# Sheet1.net
KiCad netlist of a schematic drawn in Altium Designer
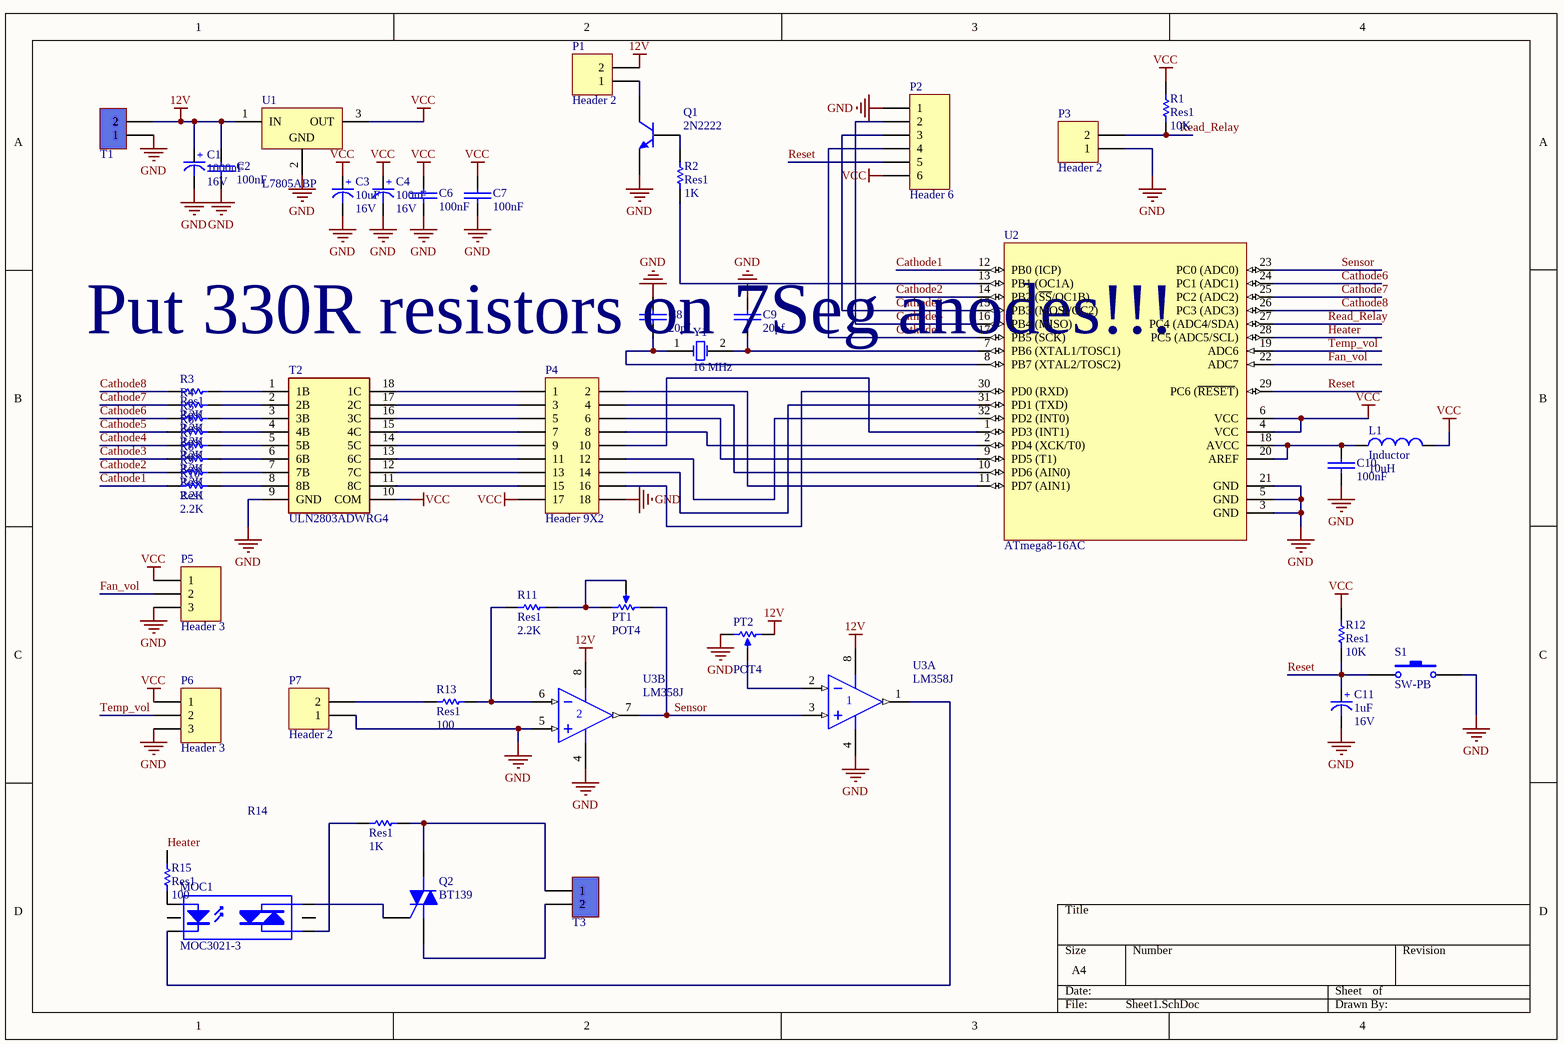
[diagram p0: Sheet1.SchDoc]

(export (version "E")
  (design (tool "Eeschema 10.0.6"))
  (components
    (comp (ref "C1")
      (value "1000uF")
      (footprint "cap 04")
      (description "Polar Capacitor")
      (fields (field (name "VOLTAGE") "16V") (field (name "DESIGNER") "Saeid Jorablo"))
      (libsource (lib "My_Library") (part "Cap-Polar"))
    )
    (comp (ref "C2")
      (value "100nF")
      (footprint "Cap - 100nF")
      (description "Bipolar Capacitor")
      (fields (field (name "VOLTAGE") "100V") (field (name "DESIGNER") "Saeid Jorablo"))
      (libsource (lib "My_Library") (part "Cap-Bipolar"))
    )
    (comp (ref "C3")
      (value "10uF")
      (footprint "cap 02")
      (description "Polar Capacitor")
      (fields (field (name "VOLTAGE") "16V") (field (name "DESIGNER") "Saeid Jorablo"))
      (libsource (lib "My_Library") (part "Cap-Polar"))
    )
    (comp (ref "C4")
      (value "100uF")
      (footprint "cap 03")
      (description "Polar Capacitor")
      (fields (field (name "VOLTAGE") "16V") (field (name "DESIGNER") "Saeid Jorablo"))
      (libsource (lib "My_Library") (part "Cap-Polar"))
    )
    (comp (ref "C6")
      (value "100nF")
      (footprint "CAP 1206 (3216X15L)")
      (description "Bipolar Capacitor")
      (fields (field (name "VOLTAGE") "100V") (field (name "DESIGNER") "Saeid Jorablo"))
      (libsource (lib "My_Library") (part "Cap-Bipolar"))
    )
    (comp (ref "C7")
      (value "100nF")
      (footprint "CAP 1206 (3216X15L)")
      (description "Bipolar Capacitor")
      (fields (field (name "VOLTAGE") "100V") (field (name "DESIGNER") "Saeid Jorablo"))
      (libsource (lib "My_Library") (part "Cap-Bipolar"))
    )
    (comp (ref "C8")
      (value "20pf")
      (footprint "CAP 1206 (3216X15L)")
      (description "Bipolar Capacitor")
      (fields (field (name "VOLTAGE") "100V") (field (name "DESIGNER") "Saeid Jorablo"))
      (libsource (lib "My_Library") (part "Cap-Bipolar"))
    )
    (comp (ref "C9")
      (value "20pf")
      (footprint "CAP 1206 (3216X15L)")
      (description "Bipolar Capacitor")
      (fields (field (name "VOLTAGE") "100V") (field (name "DESIGNER") "Saeid Jorablo"))
      (libsource (lib "My_Library") (part "Cap-Bipolar"))
    )
    (comp (ref "C10")
      (value "100nF")
      (footprint "CAP 1206 (3216X15L)")
      (description "Bipolar Capacitor")
      (fields (field (name "VOLTAGE") "100V") (field (name "DESIGNER") "Saeid Jorablo"))
      (libsource (lib "My_Library") (part "Cap-Bipolar"))
    )
    (comp (ref "C11")
      (value "1uF")
      (footprint "cap 00")
      (description "Polar Capacitor")
      (fields (field (name "VOLTAGE") "16V") (field (name "DESIGNER") "Saeid Jorablo"))
      (libsource (lib "My_Library") (part "Cap-Polar"))
    )
    (comp (ref "L1")
      (value "Inductor")
      (footprint "AXIAL-0.4")
      (fields (field (name "ALTIUM_VALUE") "10uH") (field (name "PUBLISHER") "Altium Limited"))
      (libsource (lib "Miscellaneous Devices") (part "Inductor"))
    )
    (comp (ref "MOC1")
      (value "MOC3021-3")
      (footprint "DIP-6")
      (description "Opto-Triac")
      (fields
        (field (name "PUBLISHER") "www.picpars.com")
        (field (name "DESIGNER") "Seyed Mohsen Ghasemian")
        (field (name "E-MAIL") "picpars@gmail.com")
      )
      (libsource (lib "usefully_Library") (part "MOC3021-3"))
    )
    (comp (ref "P1")
      (value "Header 2")
      (footprint "HDR1X2")
      (description "Header, 2-Pin")
      (fields (field (name "PUBLISHER") "Altium Limited"))
      (libsource (lib "Miscellaneous Connectors") (part "Header 2"))
    )
    (comp (ref "P2")
      (value "Header 6")
      (footprint "HDR1X6")
      (description "Header, 6-Pin")
      (fields (field (name "PUBLISHER") "Altium Limited"))
      (libsource (lib "Miscellaneous Connectors") (part "Header 6"))
    )
    (comp (ref "P3")
      (value "Header 2")
      (footprint "HDR1X2")
      (description "Header, 2-Pin")
      (fields (field (name "PUBLISHER") "Altium Limited"))
      (libsource (lib "Miscellaneous Connectors") (part "Header 2"))
    )
    (comp (ref "P4")
      (value "Header 9X2")
      (footprint "HDR2X9")
      (description "Header, 9-Pin, Dual row")
      (fields (field (name "PUBLISHER") "Altium Limited"))
      (libsource (lib "Miscellaneous Connectors") (part "Header 9X2"))
    )
    (comp (ref "P5")
      (value "Header 3")
      (footprint "HDR1X3")
      (description "Header, 3-Pin")
      (fields (field (name "PUBLISHER") "Altium Limited"))
      (libsource (lib "Miscellaneous Connectors") (part "Header 3"))
    )
    (comp (ref "P6")
      (value "Header 3")
      (footprint "HDR1X3")
      (description "Header, 3-Pin")
      (fields (field (name "PUBLISHER") "Altium Limited"))
      (libsource (lib "Miscellaneous Connectors") (part "Header 3"))
    )
    (comp (ref "P7")
      (value "Header 2")
      (footprint "HDR1X2")
      (description "Header, 2-Pin")
      (fields (field (name "PUBLISHER") "Altium Limited"))
      (libsource (lib "Miscellaneous Connectors") (part "Header 2"))
    )
    (comp (ref "PT1")
      (value "POT4")
      (footprint "POT4")
      (description "Variable Potentiometer top adjust")
      (fields (field (name "DESIGNER") "Seyed Mohsen Ghasemian"))
      (libsource (lib "usefully_Library") (part "POT4"))
    )
    (comp (ref "PT2")
      (value "POT4")
      (footprint "POT4")
      (description "Variable Potentiometer top adjust")
      (fields (field (name "DESIGNER") "Seyed Mohsen Ghasemian"))
      (libsource (lib "usefully_Library") (part "POT4"))
    )
    (comp (ref "Q1")
      (value "2N2222")
      (footprint "T4-TO92")
      (description "NPN")
      (fields (field (name "E-MAIL") "picpars@gmail.com"))
      (libsource (lib "usefully_Library") (part "2N2222"))
    )
    (comp (ref "Q2")
      (value "BT139")
      (footprint "TO-220-AB")
      (description "Silicon Bidirectional Triode Thyristor")
      (fields (field (name "PUBLISHER") "Altium Limited"))
      (libsource (lib "Motorola Discrete TRIAC") (part "MAC15A6"))
    )
    (comp (ref "R1")
      (value "Res1")
      (footprint "AXIAL-0.3")
      (description "Resistor")
      (fields (field (name "ALTIUM_VALUE") "10K") (field (name "PUBLISHER") "Altium Limited"))
      (libsource (lib "Miscellaneous Devices") (part "Res1"))
    )
    (comp (ref "R2")
      (value "Res1")
      (footprint "AXIAL-0.3")
      (description "Resistor")
      (fields (field (name "ALTIUM_VALUE") "1K") (field (name "PUBLISHER") "Altium Limited"))
      (libsource (lib "Miscellaneous Devices") (part "Res1"))
    )
    (comp (ref "R3")
      (value "Res1")
      (footprint "AXIAL-0.3")
      (description "Resistor")
      (fields (field (name "ALTIUM_VALUE") "2.2K") (field (name "PUBLISHER") "Altium Limited"))
      (libsource (lib "Miscellaneous Devices") (part "Res1"))
    )
    (comp (ref "R4")
      (value "Res1")
      (footprint "AXIAL-0.3")
      (description "Resistor")
      (fields (field (name "ALTIUM_VALUE") "2.2K") (field (name "PUBLISHER") "Altium Limited"))
      (libsource (lib "Miscellaneous Devices") (part "Res1"))
    )
    (comp (ref "R5")
      (value "Res1")
      (footprint "AXIAL-0.3")
      (description "Resistor")
      (fields (field (name "ALTIUM_VALUE") "2.2K") (field (name "PUBLISHER") "Altium Limited"))
      (libsource (lib "Miscellaneous Devices") (part "Res1"))
    )
    (comp (ref "R6")
      (value "Res1")
      (footprint "AXIAL-0.3")
      (description "Resistor")
      (fields (field (name "ALTIUM_VALUE") "2.2K") (field (name "PUBLISHER") "Altium Limited"))
      (libsource (lib "Miscellaneous Devices") (part "Res1"))
    )
    (comp (ref "R7")
      (value "Res1")
      (footprint "AXIAL-0.3")
      (description "Resistor")
      (fields (field (name "ALTIUM_VALUE") "2.2K") (field (name "PUBLISHER") "Altium Limited"))
      (libsource (lib "Miscellaneous Devices") (part "Res1"))
    )
    (comp (ref "R8")
      (value "Res1")
      (footprint "AXIAL-0.3")
      (description "Resistor")
      (fields (field (name "ALTIUM_VALUE") "2.2K") (field (name "PUBLISHER") "Altium Limited"))
      (libsource (lib "Miscellaneous Devices") (part "Res1"))
    )
    (comp (ref "R9")
      (value "Res1")
      (footprint "AXIAL-0.3")
      (description "Resistor")
      (fields (field (name "ALTIUM_VALUE") "2.2K") (field (name "PUBLISHER") "Altium Limited"))
      (libsource (lib "Miscellaneous Devices") (part "Res1"))
    )
    (comp (ref "R10")
      (value "Res1")
      (footprint "AXIAL-0.3")
      (description "Resistor")
      (fields (field (name "ALTIUM_VALUE") "2.2K") (field (name "PUBLISHER") "Altium Limited"))
      (libsource (lib "Miscellaneous Devices") (part "Res1"))
    )
    (comp (ref "R11")
      (value "Res1")
      (footprint "AXIAL-0.3")
      (description "Resistor")
      (fields (field (name "ALTIUM_VALUE") "2.2K") (field (name "PUBLISHER") "Altium Limited"))
      (libsource (lib "Miscellaneous Devices") (part "Res1"))
    )
    (comp (ref "R12")
      (value "Res1")
      (footprint "AXIAL-0.3")
      (description "Resistor")
      (fields (field (name "ALTIUM_VALUE") "10K") (field (name "PUBLISHER") "Altium Limited"))
      (libsource (lib "Miscellaneous Devices") (part "Res1"))
    )
    (comp (ref "R13")
      (value "Res1")
      (footprint "AXIAL-0.3")
      (description "Resistor")
      (fields (field (name "ALTIUM_VALUE") "100") (field (name "PUBLISHER") "Altium Limited"))
      (libsource (lib "Miscellaneous Devices") (part "Res1"))
    )
    (comp (ref "R14")
      (value "Res1")
      (footprint "AXIAL-0.3")
      (description "Resistor")
      (fields (field (name "ALTIUM_VALUE") "1K") (field (name "PUBLISHER") "Altium Limited"))
      (libsource (lib "Miscellaneous Devices") (part "Res1"))
    )
    (comp (ref "R15")
      (value "Res1")
      (footprint "AXIAL-0.3")
      (description "Resistor")
      (fields (field (name "ALTIUM_VALUE") "100") (field (name "PUBLISHER") "Altium Limited"))
      (libsource (lib "Miscellaneous Devices") (part "Res1"))
    )
    (comp (ref "S1")
      (value "SW-PB")
      (footprint "SPST-2")
      (description "Switch")
      (fields (field (name "PUBLISHER") "Altium Limited"))
      (libsource (lib "Miscellaneous Devices") (part "SW-PB"))
    )
    (comp (ref "T1")
      (value "Terminal")
      (footprint "Terminal 1*2")
      (description "Terminal 2 Pin 250VAC 16A")
      (fields (field (name "DESIGNER") "Seyed Mohsen Ghasemain") (field (name "E-MAIL") "picpars@gmail.com"))
      (libsource (lib "usefully_Library") (part "Terminal 1*2"))
    )
    (comp (ref "T2")
      (value "ULN2803ADWRG4")
      (footprint "SamacSys:SOIC127P1030X265-18N")
      (description "Transformer")
      (fields (field (name "MOUSER PART NUMBER") "595-ULN2803ADWRG4"))
      (libsource (lib "*") (part "ULN2803ADWRG4"))
    )
    (comp (ref "T3")
      (value "Terminal")
      (footprint "Terminal 1*2")
      (description "Terminal 2 Pin 250VAC 16A")
      (fields (field (name "DESIGNER") "Seyed Mohsen Ghasemain") (field (name "E-MAIL") "picpars@gmail.com"))
      (libsource (lib "PicPars.com_usefully_Library") (part "Terminal 1*2"))
    )
    (comp (ref "U1")
      (value "L7805ABP")
      (footprint "TO220FP")
      (description "Positive Voltage Regulator, 5V, 3-Pin TO-220FP")
      (libsource (lib "STMicroelectronics Power Management Linear Regulator") (part "L7805ABP"))
    )
    (comp (ref "U2")
      (value "ATmega8-16AC")
      (footprint "32A_M")
      (description "8-Bit AVR Microcontroller with 8K Bytes of In-System Programmable Flash Memory")
      (fields (field (name "PUBLISHER") "Altium Limited"))
      (libsource (lib "Atmel Microcontroller 8-Bit AVR") (part "ATmega8-16AC"))
    )
    (comp (ref "U3")
      (value "LM358J")
      (footprint "693-02")
      (description "Dual Low-Power Operational Amplifier")
      (fields (field (name "PUBLISHER") "Altium Limited"))
      (libsource (lib "Motorola Amplifier Operational Amplifier") (part "LM358J"))
    )
    (comp (ref "Y1")
      (value "16 MHz")
      (footprint "XTAL")
      (description "XTAL Crystal")
      (libsource (lib "My_Library") (part "XTAL"))
    )
  )
  (nets
    (net (code "1") (name "/Cathode1") (class "Default")
      (node (ref "R10") (pin "1") (pinfunction "1_1") (pintype "passive"))
      (node (ref "U2") (pin "12") (pinfunction "PB0_(ICP)_12") (pintype "bidirectional"))
    )
    (net (code "2") (name "/Cathode2") (class "Default")
      (node (ref "R9") (pin "1") (pinfunction "1_1") (pintype "passive"))
      (node (ref "U2") (pin "14") (pinfunction "PB2_(~{SS}/OC1B)_14") (pintype "bidirectional"))
    )
    (net (code "3") (name "/Cathode3") (class "Default")
      (node (ref "P2") (pin "3") (pinfunction "3_3") (pintype "passive"))
      (node (ref "R8") (pin "1") (pinfunction "1_1") (pintype "passive"))
      (node (ref "U2") (pin "15") (pinfunction "PB3_(MOSI/OC2)_15") (pintype "bidirectional"))
    )
    (net (code "4") (name "/Cathode4") (class "Default")
      (node (ref "P2") (pin "2") (pinfunction "2_2") (pintype "passive"))
      (node (ref "R7") (pin "1") (pinfunction "1_1") (pintype "passive"))
      (node (ref "U2") (pin "16") (pinfunction "PB4_(MISO)_16") (pintype "bidirectional"))
    )
    (net (code "5") (name "/Cathode5") (class "Default")
      (node (ref "P2") (pin "4") (pinfunction "4_4") (pintype "passive"))
      (node (ref "R6") (pin "1") (pinfunction "1_1") (pintype "passive"))
      (node (ref "U2") (pin "17") (pinfunction "PB5_(SCK)_17") (pintype "bidirectional"))
    )
    (net (code "6") (name "/Cathode6") (class "Default")
      (node (ref "R5") (pin "1") (pinfunction "1_1") (pintype "passive"))
      (node (ref "U2") (pin "24") (pinfunction "PC1_(ADC1)_24") (pintype "bidirectional"))
    )
    (net (code "7") (name "/Cathode7") (class "Default")
      (node (ref "R4") (pin "1") (pinfunction "1_1") (pintype "passive"))
      (node (ref "U2") (pin "25") (pinfunction "PC2_(ADC2)_25") (pintype "bidirectional"))
    )
    (net (code "8") (name "/Cathode8") (class "Default")
      (node (ref "R3") (pin "1") (pinfunction "1_1") (pintype "passive"))
      (node (ref "U2") (pin "26") (pinfunction "PC3_(ADC3)_26") (pintype "bidirectional"))
    )
    (net (code "9") (name "/Fan_vol") (class "Default")
      (node (ref "P5") (pin "2") (pinfunction "2_2") (pintype "passive"))
      (node (ref "U2") (pin "22") (pinfunction "ADC7_22") (pintype "input"))
    )
    (net (code "10") (name "/Heater") (class "Default")
      (node (ref "R15") (pin "1") (pinfunction "1_1") (pintype "passive"))
      (node (ref "U2") (pin "28") (pinfunction "PC5_(ADC5/SCL)_28") (pintype "bidirectional"))
    )
    (net (code "11") (name "/Read_Relay") (class "Default")
      (node (ref "P3") (pin "2") (pinfunction "2_2") (pintype "passive"))
      (node (ref "R1") (pin "2") (pinfunction "2_2") (pintype "passive"))
      (node (ref "U2") (pin "27") (pinfunction "PC4_(ADC4/SDA)_27") (pintype "bidirectional"))
    )
    (net (code "12") (name "/Reset") (class "Default")
      (node (ref "C11") (pin "1") (pinfunction "+_1") (pintype "passive"))
      (node (ref "P2") (pin "5") (pinfunction "5_5") (pintype "passive"))
      (node (ref "R12") (pin "2") (pinfunction "2_2") (pintype "passive"))
      (node (ref "S1") (pin "1") (pinfunction "1_1") (pintype "passive"))
      (node (ref "U2") (pin "29") (pinfunction "PC6_(~{RESET})_29") (pintype "bidirectional"))
    )
    (net (code "13") (name "/Sensor") (class "Default")
      (node (ref "PT1") (pin "1") (pinfunction "TOP_1") (pintype "passive"))
      (node (ref "U2") (pin "23") (pinfunction "PC0_(ADC0)_23") (pintype "bidirectional"))
      (node (ref "U3") (pin "3") (pinfunction "IN+_3") (pintype "input"))
      (node (ref "U3") (pin "7") (pinfunction "OUT_7") (pintype "output"))
    )
    (net (code "14") (name "/Temp_vol") (class "Default")
      (node (ref "P6") (pin "2") (pinfunction "2_2") (pintype "passive"))
      (node (ref "U2") (pin "19") (pinfunction "ADC6_19") (pintype "input"))
    )
    (net (code "15") (name "12V") (class "Default")
      (node (ref "C1") (pin "1") (pinfunction "+_1") (pintype "passive"))
      (node (ref "C2") (pin "1") (pinfunction "+_1") (pintype "passive"))
      (node (ref "P1") (pin "2") (pinfunction "2_2") (pintype "passive"))
      (node (ref "PT2") (pin "2") (pinfunction "BOT_2") (pintype "passive"))
      (node (ref "T1") (pin "2") (pinfunction "2_2") (pintype "passive"))
      (node (ref "U1") (pin "1") (pinfunction "IN_1") (pintype "power_in"))
      (node (ref "U3") (pin "8") (pinfunction "V+_8") (pintype "power_in"))
    )
    (net (code "16") (name "GND") (class "Default")
      (node (ref "C1") (pin "2") (pinfunction "-_2") (pintype "passive"))
      (node (ref "C10") (pin "2") (pinfunction "-_2") (pintype "passive"))
      (node (ref "C11") (pin "2") (pinfunction "-_2") (pintype "passive"))
      (node (ref "C2") (pin "2") (pinfunction "-_2") (pintype "passive"))
      (node (ref "C3") (pin "2") (pinfunction "-_2") (pintype "passive"))
      (node (ref "C4") (pin "2") (pinfunction "-_2") (pintype "passive"))
      (node (ref "C6") (pin "2") (pinfunction "-_2") (pintype "passive"))
      (node (ref "C7") (pin "2") (pinfunction "-_2") (pintype "passive"))
      (node (ref "C8") (pin "2") (pinfunction "-_2") (pintype "passive"))
      (node (ref "C9") (pin "1") (pinfunction "+_1") (pintype "passive"))
      (node (ref "P2") (pin "1") (pinfunction "1_1") (pintype "passive"))
      (node (ref "P3") (pin "1") (pinfunction "1_1") (pintype "passive"))
      (node (ref "P4") (pin "18") (pinfunction "18_18") (pintype "passive"))
      (node (ref "P5") (pin "3") (pinfunction "3_3") (pintype "passive"))
      (node (ref "P6") (pin "3") (pinfunction "3_3") (pintype "passive"))
      (node (ref "P7") (pin "1") (pinfunction "1_1") (pintype "passive"))
      (node (ref "PT2") (pin "1") (pinfunction "TOP_1") (pintype "passive"))
      (node (ref "Q1") (pin "E") (pinfunction "E_E") (pintype "passive"))
      (node (ref "S1") (pin "2") (pinfunction "2_2") (pintype "passive"))
      (node (ref "T1") (pin "1") (pinfunction "1_1") (pintype "passive"))
      (node (ref "T2") (pin "9") (pinfunction "GND_9") (pintype "passive"))
      (node (ref "U1") (pin "2") (pinfunction "GND_2") (pintype "power_in"))
      (node (ref "U2") (pin "21") (pinfunction "GND_21") (pintype "power_in"))
      (node (ref "U2") (pin "3") (pinfunction "GND_3") (pintype "power_in"))
      (node (ref "U2") (pin "5") (pinfunction "GND_5") (pintype "power_in"))
      (node (ref "U3") (pin "4") (pinfunction "V-_4") (pintype "power_in"))
      (node (ref "U3") (pin "5") (pinfunction "IN+_5") (pintype "input"))
    )
    (net (code "17") (name "Net-(C8-+)") (class "Default")
      (node (ref "C8") (pin "1") (pinfunction "+_1") (pintype "passive"))
      (node (ref "U2") (pin "8") (pinfunction "PB7_(XTAL2/TOSC2)_8") (pintype "bidirectional"))
      (node (ref "Y1") (pin "1") (pinfunction "OSC1_1") (pintype "passive"))
    )
    (net (code "18") (name "Net-(C9--)") (class "Default")
      (node (ref "C9") (pin "2") (pinfunction "-_2") (pintype "passive"))
      (node (ref "U2") (pin "7") (pinfunction "PB6_(XTAL1/TOSC1)_7") (pintype "bidirectional"))
      (node (ref "Y1") (pin "2") (pinfunction "OSC2_2") (pintype "passive"))
    )
    (net (code "19") (name "Net-(C10-+)") (class "Default")
      (node (ref "C10") (pin "1") (pinfunction "+_1") (pintype "passive"))
      (node (ref "L1") (pin "1") (pinfunction "1_1") (pintype "passive"))
      (node (ref "U2") (pin "18") (pinfunction "AVCC_18") (pintype "power_in"))
      (node (ref "U2") (pin "20") (pinfunction "AREF_20") (pintype "passive"))
    )
    (net (code "20") (name "Net-(MOC1-A)") (class "Default")
      (node (ref "MOC1") (pin "1") (pinfunction "A_1") (pintype "passive"))
      (node (ref "R15") (pin "2") (pinfunction "2_2") (pintype "passive"))
    )
    (net (code "21") (name "Net-(MOC1-A{slash}K-Pad6)") (class "Default")
      (node (ref "MOC1") (pin "6") (pinfunction "A/K_6") (pintype "passive"))
      (node (ref "R14") (pin "1") (pinfunction "1_1") (pintype "passive"))
    )
    (net (code "22") (name "Net-(MOC1-K)") (class "Default")
      (node (ref "MOC1") (pin "2") (pinfunction "K_2") (pintype "passive"))
      (node (ref "U3") (pin "1") (pinfunction "OUT_1") (pintype "output"))
    )
    (net (code "23") (name "Net-(P1-Pad1)") (class "Default")
      (node (ref "P1") (pin "1") (pinfunction "1_1") (pintype "passive"))
      (node (ref "Q1") (pin "C") (pinfunction "C_C") (pintype "passive"))
    )
    (net (code "24") (name "Net-(P7-Pad2)") (class "Default")
      (node (ref "P7") (pin "2") (pinfunction "2_2") (pintype "passive"))
      (node (ref "R13") (pin "1") (pinfunction "1_1") (pintype "passive"))
    )
    (net (code "25") (name "Net-(PT1-BOT)") (class "Default")
      (node (ref "PT1") (pin "2") (pinfunction "BOT_2") (pintype "passive"))
      (node (ref "PT1") (pin "3") (pinfunction "TAP_3") (pintype "passive"))
      (node (ref "R11") (pin "2") (pinfunction "2_2") (pintype "passive"))
    )
    (net (code "26") (name "Net-(PT2-TAP)") (class "Default")
      (node (ref "PT2") (pin "3") (pinfunction "TAP_3") (pintype "passive"))
      (node (ref "U3") (pin "2") (pinfunction "IN-_2") (pintype "input"))
    )
    (net (code "27") (name "Net-(Q1-PadB)") (class "Default")
      (node (ref "Q1") (pin "B") (pinfunction "B_B") (pintype "passive"))
      (node (ref "R2") (pin "1") (pinfunction "1_1") (pintype "passive"))
    )
    (net (code "28") (name "Net-(Q2-G)") (class "Default")
      (node (ref "MOC1") (pin "4") (pinfunction "A/K_4") (pintype "passive"))
      (node (ref "Q2") (pin "3") (pinfunction "G_3") (pintype "passive"))
    )
    (net (code "29") (name "Net-(Q2-M1)") (class "Default")
      (node (ref "Q2") (pin "1") (pinfunction "M1_1") (pintype "passive"))
      (node (ref "T3") (pin "2") (pinfunction "2_2") (pintype "passive"))
    )
    (net (code "30") (name "Net-(Q2-M2)") (class "Default")
      (node (ref "Q2") (pin "2") (pinfunction "M2_2") (pintype "passive"))
      (node (ref "R14") (pin "2") (pinfunction "2_2") (pintype "passive"))
      (node (ref "T3") (pin "1") (pinfunction "1_1") (pintype "passive"))
    )
    (net (code "31") (name "Net-(T2-1B)") (class "Default")
      (node (ref "R3") (pin "2") (pinfunction "2_2") (pintype "passive"))
      (node (ref "T2") (pin "1") (pinfunction "1B_1") (pintype "passive"))
    )
    (net (code "32") (name "Net-(T2-1C)") (class "Default")
      (node (ref "P4") (pin "1") (pinfunction "1_1") (pintype "passive"))
      (node (ref "T2") (pin "18") (pinfunction "1C_18") (pintype "passive"))
    )
    (net (code "33") (name "Net-(T2-2B)") (class "Default")
      (node (ref "R4") (pin "2") (pinfunction "2_2") (pintype "passive"))
      (node (ref "T2") (pin "2") (pinfunction "2B_2") (pintype "passive"))
    )
    (net (code "34") (name "Net-(T2-2C)") (class "Default")
      (node (ref "P4") (pin "3") (pinfunction "3_3") (pintype "passive"))
      (node (ref "T2") (pin "17") (pinfunction "2C_17") (pintype "passive"))
    )
    (net (code "35") (name "Net-(T2-3B)") (class "Default")
      (node (ref "R5") (pin "2") (pinfunction "2_2") (pintype "passive"))
      (node (ref "T2") (pin "3") (pinfunction "3B_3") (pintype "passive"))
    )
    (net (code "36") (name "Net-(T2-3C)") (class "Default")
      (node (ref "P4") (pin "5") (pinfunction "5_5") (pintype "passive"))
      (node (ref "T2") (pin "16") (pinfunction "3C_16") (pintype "passive"))
    )
    (net (code "37") (name "Net-(T2-4B)") (class "Default")
      (node (ref "R6") (pin "2") (pinfunction "2_2") (pintype "passive"))
      (node (ref "T2") (pin "4") (pinfunction "4B_4") (pintype "passive"))
    )
    (net (code "38") (name "Net-(T2-4C)") (class "Default")
      (node (ref "P4") (pin "7") (pinfunction "7_7") (pintype "passive"))
      (node (ref "T2") (pin "15") (pinfunction "4C_15") (pintype "passive"))
    )
    (net (code "39") (name "Net-(T2-5B)") (class "Default")
      (node (ref "R7") (pin "2") (pinfunction "2_2") (pintype "passive"))
      (node (ref "T2") (pin "5") (pinfunction "5B_5") (pintype "passive"))
    )
    (net (code "40") (name "Net-(T2-5C)") (class "Default")
      (node (ref "P4") (pin "9") (pinfunction "9_9") (pintype "passive"))
      (node (ref "T2") (pin "14") (pinfunction "5C_14") (pintype "passive"))
    )
    (net (code "41") (name "Net-(T2-6B)") (class "Default")
      (node (ref "R8") (pin "2") (pinfunction "2_2") (pintype "passive"))
      (node (ref "T2") (pin "6") (pinfunction "6B_6") (pintype "passive"))
    )
    (net (code "42") (name "Net-(T2-6C)") (class "Default")
      (node (ref "P4") (pin "11") (pinfunction "11_11") (pintype "passive"))
      (node (ref "T2") (pin "13") (pinfunction "6C_13") (pintype "passive"))
    )
    (net (code "43") (name "Net-(T2-7B)") (class "Default")
      (node (ref "R9") (pin "2") (pinfunction "2_2") (pintype "passive"))
      (node (ref "T2") (pin "7") (pinfunction "7B_7") (pintype "passive"))
    )
    (net (code "44") (name "Net-(T2-7C)") (class "Default")
      (node (ref "P4") (pin "13") (pinfunction "13_13") (pintype "passive"))
      (node (ref "T2") (pin "12") (pinfunction "7C_12") (pintype "passive"))
    )
    (net (code "45") (name "Net-(T2-8B)") (class "Default")
      (node (ref "R10") (pin "2") (pinfunction "2_2") (pintype "passive"))
      (node (ref "T2") (pin "8") (pinfunction "8B_8") (pintype "passive"))
    )
    (net (code "46") (name "Net-(T2-8C)") (class "Default")
      (node (ref "P4") (pin "15") (pinfunction "15_15") (pintype "passive"))
      (node (ref "T2") (pin "11") (pinfunction "8C_11") (pintype "passive"))
    )
    (net (code "47") (name "Net-(U2-PB1_(OC1A))") (class "Default")
      (node (ref "R2") (pin "2") (pinfunction "2_2") (pintype "passive"))
      (node (ref "U2") (pin "13") (pinfunction "PB1_(OC1A)_13") (pintype "bidirectional"))
    )
    (net (code "48") (name "Net-(U2-PD0_(RXD))") (class "Default")
      (node (ref "P4") (pin "16") (pinfunction "16_16") (pintype "passive"))
      (node (ref "U2") (pin "30") (pinfunction "PD0_(RXD)_30") (pintype "bidirectional"))
    )
    (net (code "49") (name "Net-(U2-PD1_(TXD))") (class "Default")
      (node (ref "P4") (pin "14") (pinfunction "14_14") (pintype "passive"))
      (node (ref "U2") (pin "31") (pinfunction "PD1_(TXD)_31") (pintype "bidirectional"))
    )
    (net (code "50") (name "Net-(U2-PD2_(INT0))") (class "Default")
      (node (ref "P4") (pin "12") (pinfunction "12_12") (pintype "passive"))
      (node (ref "U2") (pin "32") (pinfunction "PD2_(INT0)_32") (pintype "bidirectional"))
    )
    (net (code "51") (name "Net-(U2-PD3_(INT1))") (class "Default")
      (node (ref "P4") (pin "10") (pinfunction "10_10") (pintype "passive"))
      (node (ref "U2") (pin "1") (pinfunction "PD3_(INT1)_1") (pintype "bidirectional"))
    )
    (net (code "52") (name "Net-(U2-PD4_(XCK{slash}T0))") (class "Default")
      (node (ref "P4") (pin "8") (pinfunction "8_8") (pintype "passive"))
      (node (ref "U2") (pin "2") (pinfunction "PD4_(XCK/T0)_2") (pintype "bidirectional"))
    )
    (net (code "53") (name "Net-(U2-PD5_(T1))") (class "Default")
      (node (ref "P4") (pin "6") (pinfunction "6_6") (pintype "passive"))
      (node (ref "U2") (pin "9") (pinfunction "PD5_(T1)_9") (pintype "bidirectional"))
    )
    (net (code "54") (name "Net-(U2-PD6_(AIN0))") (class "Default")
      (node (ref "P4") (pin "4") (pinfunction "4_4") (pintype "passive"))
      (node (ref "U2") (pin "10") (pinfunction "PD6_(AIN0)_10") (pintype "bidirectional"))
    )
    (net (code "55") (name "Net-(U2-PD7_(AIN1))") (class "Default")
      (node (ref "P4") (pin "2") (pinfunction "2_2") (pintype "passive"))
      (node (ref "U2") (pin "11") (pinfunction "PD7_(AIN1)_11") (pintype "bidirectional"))
    )
    (net (code "56") (name "Net-(U3B-IN-)") (class "Default")
      (node (ref "R11") (pin "1") (pinfunction "1_1") (pintype "passive"))
      (node (ref "R13") (pin "2") (pinfunction "2_2") (pintype "passive"))
      (node (ref "U3") (pin "6") (pinfunction "IN-_6") (pintype "input"))
    )
    (net (code "57") (name "VCC") (class "Default")
      (node (ref "C3") (pin "1") (pinfunction "+_1") (pintype "passive"))
      (node (ref "C4") (pin "1") (pinfunction "+_1") (pintype "passive"))
      (node (ref "C6") (pin "1") (pinfunction "+_1") (pintype "passive"))
      (node (ref "C7") (pin "1") (pinfunction "+_1") (pintype "passive"))
      (node (ref "L1") (pin "2") (pinfunction "2_2") (pintype "passive"))
      (node (ref "P2") (pin "6") (pinfunction "6_6") (pintype "passive"))
      (node (ref "P4") (pin "17") (pinfunction "17_17") (pintype "passive"))
      (node (ref "P5") (pin "1") (pinfunction "1_1") (pintype "passive"))
      (node (ref "P6") (pin "1") (pinfunction "1_1") (pintype "passive"))
      (node (ref "R1") (pin "1") (pinfunction "1_1") (pintype "passive"))
      (node (ref "R12") (pin "1") (pinfunction "1_1") (pintype "passive"))
      (node (ref "T2") (pin "10") (pinfunction "COM_10") (pintype "passive"))
      (node (ref "U1") (pin "3") (pinfunction "OUT_3") (pintype "power_in"))
      (node (ref "U2") (pin "4") (pinfunction "VCC_4") (pintype "power_in"))
      (node (ref "U2") (pin "6") (pinfunction "VCC_6") (pintype "power_in"))
    )
    (net (code "58") (name "unconnected-(MOC1-NC-Pad3)") (class "Default")
      (node (ref "MOC1") (pin "3") (pinfunction "NC_3") (pintype "passive"))
    )
    (net (code "59") (name "unconnected-(MOC1-NC-Pad5)") (class "Default")
      (node (ref "MOC1") (pin "5") (pinfunction "NC_5") (pintype "passive"))
    )
  )
)
